# SML-230109PCB1__LCD.net
KiCad netlist of a schematic drawn in Altium Designer
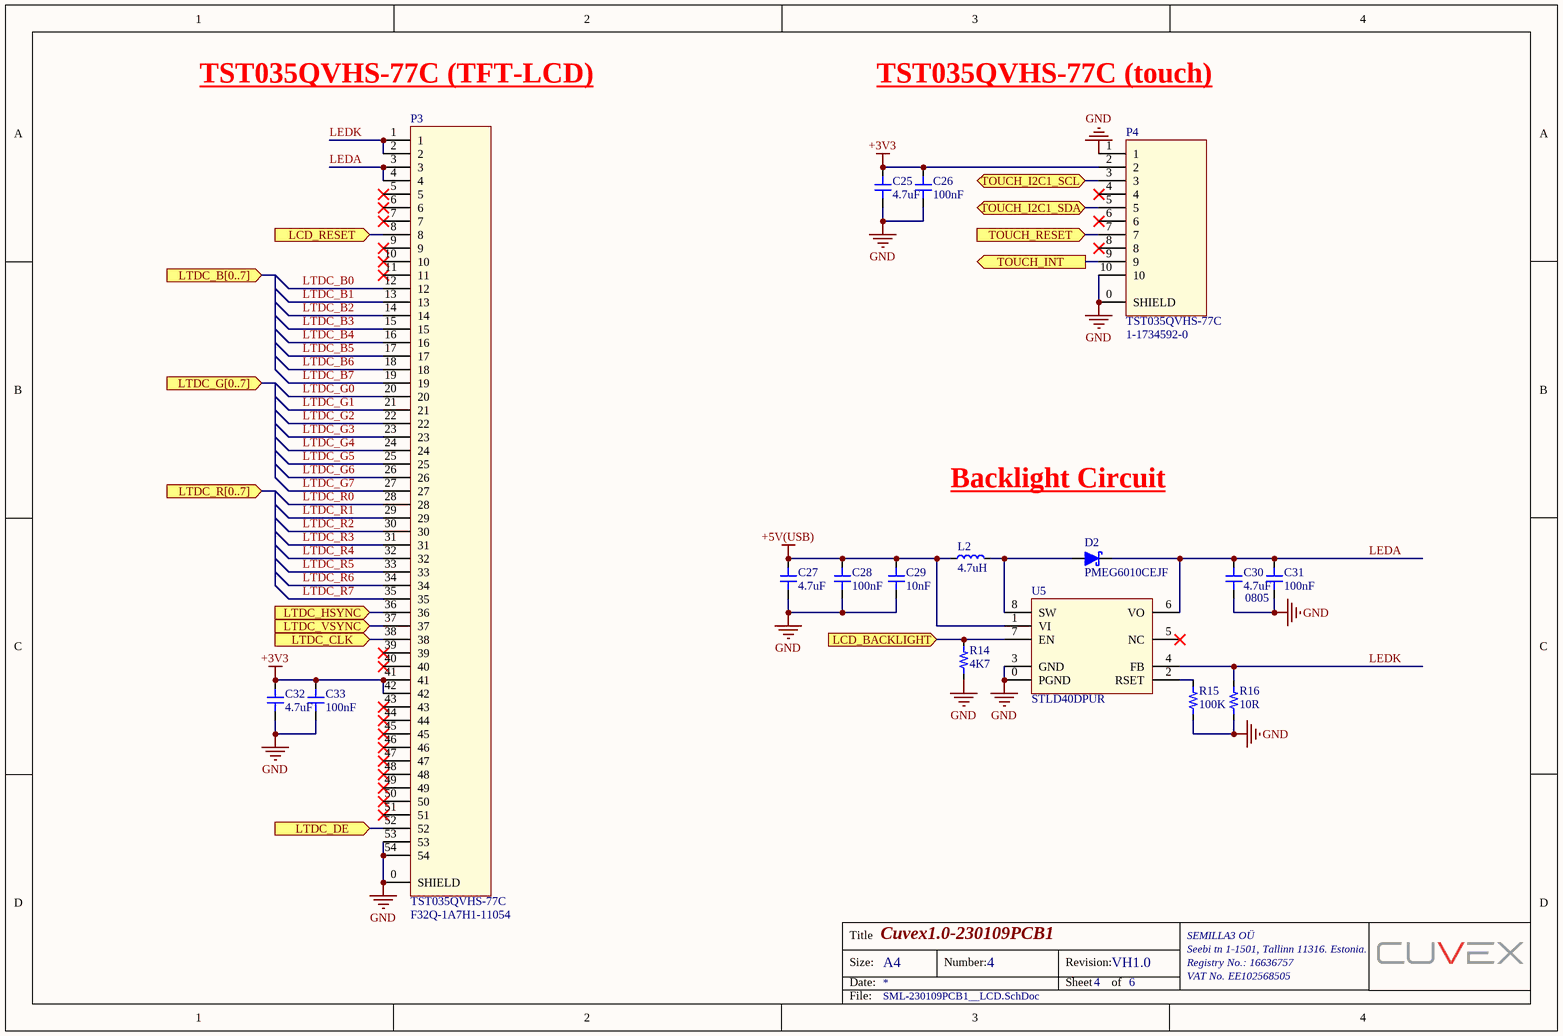
[diagram p0: SML-230109PCB1__LCD.SchDoc]

(export (version "E")
  (design (tool "Eeschema 10.0.6"))
  (components
    (comp (ref "C25")
      (value "4.7uF")
      (footprint "[G] CAP-MLCC__0603")
      (description "CAP MLCC 0603")
      (fields (field (name "VOLTAGE") "010") (field (name "Comment") "."))
      (libsource (lib "DEB_LIB_SCH_22-03") (part "CAP_MLCC_0603"))
    )
    (comp (ref "C26")
      (value "100nF")
      (footprint "[G] CAP-MLCC__0603")
      (description "CAP MLCC 0603")
      (fields (field (name "VOLTAGE") "010") (field (name "Comment") "."))
      (libsource (lib "DEB_LIB_SCH_22-03") (part "CAP_MLCC_0603"))
    )
    (comp (ref "C27")
      (value "4.7uF")
      (footprint "[G] CAP-MLCC__0603")
      (description "CAP MLCC 0603")
      (fields (field (name "VOLTAGE") "010") (field (name "Comment") "."))
      (libsource (lib "DEB_LIB_SCH_22-03") (part "CAP_MLCC_0603"))
    )
    (comp (ref "C28")
      (value "100nF")
      (footprint "[G] CAP-MLCC__0603")
      (description "CAP MLCC 0603")
      (fields (field (name "VOLTAGE") "010") (field (name "Comment") "."))
      (libsource (lib "DEB_LIB_SCH_22-03") (part "CAP_MLCC_0603"))
    )
    (comp (ref "C29")
      (value "10nF")
      (footprint "[G] CAP-MLCC__0603")
      (description "CAP MLCC 0603")
      (fields (field (name "VOLTAGE") "010") (field (name "Comment") "."))
      (libsource (lib "DEB_LIB_SCH_22-03") (part "CAP_MLCC_0603"))
    )
    (comp (ref "C30")
      (value "4.7uF")
      (footprint "[G] CAP-MLCC__0805")
      (description "CAP MLCC 0805")
      (fields
        (field (name "VOLTAGE") "050")
        (field (name "[06] - PACKAGE") "0805")
        (field (name "Comment") ".")
      )
      (libsource (lib "DEB_LIB_SCH_22-03") (part "CAP_MLCC_0805"))
    )
    (comp (ref "C31")
      (value "100nF")
      (footprint "[G] CAP-MLCC__0603")
      (description "CAP MLCC 0603")
      (fields (field (name "VOLTAGE") "050") (field (name "Comment") "."))
      (libsource (lib "DEB_LIB_SCH_22-03") (part "CAP_MLCC_0603"))
    )
    (comp (ref "C32")
      (value "4.7uF")
      (footprint "[G] CAP-MLCC__0603")
      (description "CAP MLCC 0603")
      (fields (field (name "VOLTAGE") "010") (field (name "Comment") "."))
      (libsource (lib "DEB_LIB_SCH_22-03") (part "CAP_MLCC_0603"))
    )
    (comp (ref "C33")
      (value "100nF")
      (footprint "[G] CAP-MLCC__0603")
      (description "CAP MLCC 0603")
      (fields (field (name "VOLTAGE") "010") (field (name "Comment") "."))
      (libsource (lib "DEB_LIB_SCH_22-03") (part "CAP_MLCC_0603"))
    )
    (comp (ref "D2")
      (value ".")
      (footprint "[G] SOD-323__W")
      (description "DIODE SCHOTTKY & RECTIFIER, SOD-323F, Vf=570mV, If=1A, Vr=60V, Ir=50uA")
      (fields (field (name "[01] - MPN CODE") "PMEG6010CEJF"))
      (libsource (lib "DEB_LIB_SCH_22-03") (part "PMEG6010CEJF"))
    )
    (comp (ref "L2")
      (value "4.7uH")
      (footprint "IND__LQH32PH__3'2x2'5x1'55mm")
      (description "IND Murata, LQH32PHxxx, 4'7uH")
      (fields (field (name "Comment") "."))
      (libsource (lib "DEB_LIB_SCH_22-03") (part "LQH32PH4R7NN0L"))
    )
    (comp (ref "P3")
      (value ".")
      (footprint "CONN-FFC/FPC__AMPHENOL__54P-TOP__F32Q-1A7H1-11054__INV")
      (description "CONN FFC/FPC, AMPHENOL, right angle, 54pin (0'5mm), top contact")
      (fields (field (name "TFT-LCD") "TST035QVHS-77C") (field (name "[01] - MPN CODE") "F32Q-1A7H1-11054"))
      (libsource (lib "DEB_LIB_SCH_22-03") (part "F32Q-1A7H1-11054"))
    )
    (comp (ref "P4")
      (value ".")
      (footprint "CONN-FFC/FPC__TE__10P-BOT__1-1734592-0__INV")
      (description "CONN FFC/FPC, TE, right angle, 10pin (0'5mm), bot contact")
      (fields (field (name "TFT-LCD") "TST035QVHS-77C") (field (name "[01] - MPN CODE") "1-1734592-0"))
      (libsource (lib "DEB_LIB_SCH_22-03") (part "1-1734592-0"))
    )
    (comp (ref "R14")
      (value "4K7")
      (footprint "[G] RES-CHIP__0603")
      (description "RES SMD 0603 [G]")
      (fields (field (name "TOLERANCE") "1%") (field (name "Comment") "."))
      (libsource (lib "DEB_LIB_SCH_22-03") (part "RES_SMD_0603"))
    )
    (comp (ref "R15")
      (value "100K")
      (footprint "[G] RES-CHIP__0603")
      (description "RES SMD 0603 [G]")
      (fields (field (name "TOLERANCE") "1%") (field (name "Comment") "."))
      (libsource (lib "DEB_LIB_SCH_22-03") (part "RES_SMD_0603"))
    )
    (comp (ref "R16")
      (value "10R")
      (footprint "[G] RES-CHIP__0603")
      (description "RES SMD 0603 [G]")
      (fields (field (name "TOLERANCE") "1%") (field (name "Comment") "."))
      (libsource (lib "DEB_LIB_SCH_22-03") (part "RES_SMD_0603"))
    )
    (comp (ref "U5")
      (value ".")
      (footprint "IC-DRV-LED__STLD40DPUR__QFN-8(3X3)")
      (description "IC DRV LED BOOST, 1 output, Vdd=3'00-5'5V, Vout≤37V, Iout=20mA")
      (fields (field (name "[01] - MPN CODE") "STLD40DPUR"))
      (libsource (lib "DEB_LIB_SCH_22-03") (part "STLD40DPUR"))
    )
  )
  (nets
    (net (code "1") (name "+3V3") (class "Default")
      (node (ref "C25") (pin "2") (pinfunction "2_2") (pintype "passive"))
      (node (ref "C26") (pin "2") (pinfunction "2_2") (pintype "passive"))
      (node (ref "C32") (pin "2") (pinfunction "2_2") (pintype "passive"))
      (node (ref "C33") (pin "2") (pinfunction "2_2") (pintype "passive"))
      (node (ref "P3") (pin "41") (pinfunction "41_41") (pintype "passive"))
      (node (ref "P3") (pin "42") (pinfunction "42_42") (pintype "passive"))
      (node (ref "P4") (pin "2") (pinfunction "2_2") (pintype "passive"))
    )
    (net (code "2") (name "+5V(USB)") (class "Default")
      (node (ref "C27") (pin "2") (pinfunction "2_2") (pintype "passive"))
      (node (ref "C28") (pin "2") (pinfunction "2_2") (pintype "passive"))
      (node (ref "C29") (pin "2") (pinfunction "2_2") (pintype "passive"))
      (node (ref "L2") (pin "1") (pinfunction "1_1") (pintype "passive"))
      (node (ref "U5") (pin "1") (pinfunction "VI_1") (pintype "passive"))
    )
    (net (code "3") (name "/LCD_BACKLIGHT") (class "Default")
      (node (ref "R14") (pin "1") (pinfunction "1_1") (pintype "passive"))
      (node (ref "U5") (pin "7") (pinfunction "EN_7") (pintype "passive"))
    )
    (net (code "4") (name "/LCD_RESET") (class "Default")
      (node (ref "P3") (pin "8") (pinfunction "8_8") (pintype "passive"))
    )
    (net (code "5") (name "/LEDA") (class "Default")
      (node (ref "C30") (pin "2") (pinfunction "2_2") (pintype "passive"))
      (node (ref "C31") (pin "2") (pinfunction "2_2") (pintype "passive"))
      (node (ref "D2") (pin "K") (pinfunction "K_K") (pintype "passive"))
      (node (ref "P3") (pin "3") (pinfunction "3_3") (pintype "passive"))
      (node (ref "P3") (pin "4") (pinfunction "4_4") (pintype "passive"))
      (node (ref "U5") (pin "6") (pinfunction "VO_6") (pintype "passive"))
    )
    (net (code "6") (name "/LEDK") (class "Default")
      (node (ref "P3") (pin "1") (pinfunction "1_1") (pintype "passive"))
      (node (ref "P3") (pin "2") (pinfunction "2_2") (pintype "passive"))
      (node (ref "R16") (pin "2") (pinfunction "2_2") (pintype "passive"))
      (node (ref "U5") (pin "4") (pinfunction "FB_4") (pintype "passive"))
    )
    (net (code "7") (name "/LTDC_B0") (class "Default")
      (node (ref "P3") (pin "12") (pinfunction "12_12") (pintype "passive"))
    )
    (net (code "8") (name "/LTDC_B1") (class "Default")
      (node (ref "P3") (pin "13") (pinfunction "13_13") (pintype "passive"))
    )
    (net (code "9") (name "/LTDC_B2") (class "Default")
      (node (ref "P3") (pin "14") (pinfunction "14_14") (pintype "passive"))
    )
    (net (code "10") (name "/LTDC_B3") (class "Default")
      (node (ref "P3") (pin "15") (pinfunction "15_15") (pintype "passive"))
    )
    (net (code "11") (name "/LTDC_B4") (class "Default")
      (node (ref "P3") (pin "16") (pinfunction "16_16") (pintype "passive"))
    )
    (net (code "12") (name "/LTDC_B5") (class "Default")
      (node (ref "P3") (pin "17") (pinfunction "17_17") (pintype "passive"))
    )
    (net (code "13") (name "/LTDC_B6") (class "Default")
      (node (ref "P3") (pin "18") (pinfunction "18_18") (pintype "passive"))
    )
    (net (code "14") (name "/LTDC_B7") (class "Default")
      (node (ref "P3") (pin "19") (pinfunction "19_19") (pintype "passive"))
    )
    (net (code "16") (name "/LTDC_CLK") (class "Default")
      (node (ref "P3") (pin "38") (pinfunction "38_38") (pintype "passive"))
    )
    (net (code "17") (name "/LTDC_DE") (class "Default")
      (node (ref "P3") (pin "52") (pinfunction "52_52") (pintype "passive"))
    )
    (net (code "18") (name "/LTDC_G0") (class "Default")
      (node (ref "P3") (pin "20") (pinfunction "20_20") (pintype "passive"))
    )
    (net (code "19") (name "/LTDC_G1") (class "Default")
      (node (ref "P3") (pin "21") (pinfunction "21_21") (pintype "passive"))
    )
    (net (code "20") (name "/LTDC_G2") (class "Default")
      (node (ref "P3") (pin "22") (pinfunction "22_22") (pintype "passive"))
    )
    (net (code "21") (name "/LTDC_G3") (class "Default")
      (node (ref "P3") (pin "23") (pinfunction "23_23") (pintype "passive"))
    )
    (net (code "22") (name "/LTDC_G4") (class "Default")
      (node (ref "P3") (pin "24") (pinfunction "24_24") (pintype "passive"))
    )
    (net (code "23") (name "/LTDC_G5") (class "Default")
      (node (ref "P3") (pin "25") (pinfunction "25_25") (pintype "passive"))
    )
    (net (code "24") (name "/LTDC_G6") (class "Default")
      (node (ref "P3") (pin "26") (pinfunction "26_26") (pintype "passive"))
    )
    (net (code "25") (name "/LTDC_G7") (class "Default")
      (node (ref "P3") (pin "27") (pinfunction "27_27") (pintype "passive"))
    )
    (net (code "27") (name "/LTDC_HSYNC") (class "Default")
      (node (ref "P3") (pin "36") (pinfunction "36_36") (pintype "passive"))
    )
    (net (code "28") (name "/LTDC_R0") (class "Default")
      (node (ref "P3") (pin "28") (pinfunction "28_28") (pintype "passive"))
    )
    (net (code "29") (name "/LTDC_R1") (class "Default")
      (node (ref "P3") (pin "29") (pinfunction "29_29") (pintype "passive"))
    )
    (net (code "30") (name "/LTDC_R2") (class "Default")
      (node (ref "P3") (pin "30") (pinfunction "30_30") (pintype "passive"))
    )
    (net (code "31") (name "/LTDC_R3") (class "Default")
      (node (ref "P3") (pin "31") (pinfunction "31_31") (pintype "passive"))
    )
    (net (code "32") (name "/LTDC_R4") (class "Default")
      (node (ref "P3") (pin "32") (pinfunction "32_32") (pintype "passive"))
    )
    (net (code "33") (name "/LTDC_R5") (class "Default")
      (node (ref "P3") (pin "33") (pinfunction "33_33") (pintype "passive"))
    )
    (net (code "34") (name "/LTDC_R6") (class "Default")
      (node (ref "P3") (pin "34") (pinfunction "34_34") (pintype "passive"))
    )
    (net (code "35") (name "/LTDC_R7") (class "Default")
      (node (ref "P3") (pin "35") (pinfunction "35_35") (pintype "passive"))
    )
    (net (code "37") (name "/LTDC_VSYNC") (class "Default")
      (node (ref "P3") (pin "37") (pinfunction "37_37") (pintype "passive"))
    )
    (net (code "38") (name "/TOUCH_I2C1_SCL") (class "Default")
      (node (ref "P4") (pin "3") (pinfunction "3_3") (pintype "passive"))
    )
    (net (code "39") (name "/TOUCH_I2C1_SDA") (class "Default")
      (node (ref "P4") (pin "5") (pinfunction "5_5") (pintype "passive"))
    )
    (net (code "40") (name "/TOUCH_INT") (class "Default")
      (node (ref "P4") (pin "9") (pinfunction "9_9") (pintype "passive"))
    )
    (net (code "41") (name "/TOUCH_RESET") (class "Default")
      (node (ref "P4") (pin "7") (pinfunction "7_7") (pintype "passive"))
    )
    (net (code "42") (name "GND") (class "Default")
      (node (ref "C25") (pin "1") (pinfunction "1_1") (pintype "passive"))
      (node (ref "C26") (pin "1") (pinfunction "1_1") (pintype "passive"))
      (node (ref "C27") (pin "1") (pinfunction "1_1") (pintype "passive"))
      (node (ref "C28") (pin "1") (pinfunction "1_1") (pintype "passive"))
      (node (ref "C29") (pin "1") (pinfunction "1_1") (pintype "passive"))
      (node (ref "C30") (pin "1") (pinfunction "1_1") (pintype "passive"))
      (node (ref "C31") (pin "1") (pinfunction "1_1") (pintype "passive"))
      (node (ref "C32") (pin "1") (pinfunction "1_1") (pintype "passive"))
      (node (ref "C33") (pin "1") (pinfunction "1_1") (pintype "passive"))
      (node (ref "P3") (pin "0") (pinfunction "SHIELD_0") (pintype "passive"))
      (node (ref "P3") (pin "53") (pinfunction "53_53") (pintype "passive"))
      (node (ref "P3") (pin "54") (pinfunction "54_54") (pintype "passive"))
      (node (ref "P4") (pin "0") (pinfunction "SHIELD_0") (pintype "passive"))
      (node (ref "P4") (pin "1") (pinfunction "1_1") (pintype "passive"))
      (node (ref "P4") (pin "10") (pinfunction "10_10") (pintype "passive"))
      (node (ref "R14") (pin "2") (pinfunction "2_2") (pintype "passive"))
      (node (ref "R15") (pin "1") (pinfunction "1_1") (pintype "passive"))
      (node (ref "R16") (pin "1") (pinfunction "1_1") (pintype "passive"))
      (node (ref "U5") (pin "0") (pinfunction "PGND_0") (pintype "passive"))
      (node (ref "U5") (pin "3") (pinfunction "GND_3") (pintype "passive"))
    )
    (net (code "43") (name "Net-(U5-RSET)") (class "Default")
      (node (ref "R15") (pin "2") (pinfunction "2_2") (pintype "passive"))
      (node (ref "U5") (pin "2") (pinfunction "RSET_2") (pintype "passive"))
    )
    (net (code "44") (name "Net-(U5-SW)") (class "Default")
      (node (ref "D2") (pin "A") (pinfunction "A_A") (pintype "passive"))
      (node (ref "L2") (pin "2") (pinfunction "2_2") (pintype "passive"))
      (node (ref "U5") (pin "8") (pinfunction "SW_8") (pintype "passive"))
    )
    (net (code "45") (name "unconnected-(P3-Pad5)") (class "Default")
      (node (ref "P3") (pin "5") (pinfunction "5_5") (pintype "passive+no_connect"))
    )
    (net (code "46") (name "unconnected-(P3-Pad6)") (class "Default")
      (node (ref "P3") (pin "6") (pinfunction "6_6") (pintype "passive+no_connect"))
    )
    (net (code "47") (name "unconnected-(P3-Pad7)") (class "Default")
      (node (ref "P3") (pin "7") (pinfunction "7_7") (pintype "passive+no_connect"))
    )
    (net (code "48") (name "unconnected-(P3-Pad9)") (class "Default")
      (node (ref "P3") (pin "9") (pinfunction "9_9") (pintype "passive+no_connect"))
    )
    (net (code "49") (name "unconnected-(P3-Pad10)") (class "Default")
      (node (ref "P3") (pin "10") (pinfunction "10_10") (pintype "passive+no_connect"))
    )
    (net (code "50") (name "unconnected-(P3-Pad11)") (class "Default")
      (node (ref "P3") (pin "11") (pinfunction "11_11") (pintype "passive+no_connect"))
    )
    (net (code "51") (name "unconnected-(P3-Pad39)") (class "Default")
      (node (ref "P3") (pin "39") (pinfunction "39_39") (pintype "passive+no_connect"))
    )
    (net (code "52") (name "unconnected-(P3-Pad40)") (class "Default")
      (node (ref "P3") (pin "40") (pinfunction "40_40") (pintype "passive+no_connect"))
    )
    (net (code "53") (name "unconnected-(P3-Pad43)") (class "Default")
      (node (ref "P3") (pin "43") (pinfunction "43_43") (pintype "passive+no_connect"))
    )
    (net (code "54") (name "unconnected-(P3-Pad44)") (class "Default")
      (node (ref "P3") (pin "44") (pinfunction "44_44") (pintype "passive+no_connect"))
    )
    (net (code "55") (name "unconnected-(P3-Pad45)") (class "Default")
      (node (ref "P3") (pin "45") (pinfunction "45_45") (pintype "passive+no_connect"))
    )
    (net (code "56") (name "unconnected-(P3-Pad46)") (class "Default")
      (node (ref "P3") (pin "46") (pinfunction "46_46") (pintype "passive+no_connect"))
    )
    (net (code "57") (name "unconnected-(P3-Pad47)") (class "Default")
      (node (ref "P3") (pin "47") (pinfunction "47_47") (pintype "passive+no_connect"))
    )
    (net (code "58") (name "unconnected-(P3-Pad48)") (class "Default")
      (node (ref "P3") (pin "48") (pinfunction "48_48") (pintype "passive+no_connect"))
    )
    (net (code "59") (name "unconnected-(P3-Pad49)") (class "Default")
      (node (ref "P3") (pin "49") (pinfunction "49_49") (pintype "passive+no_connect"))
    )
    (net (code "60") (name "unconnected-(P3-Pad50)") (class "Default")
      (node (ref "P3") (pin "50") (pinfunction "50_50") (pintype "passive+no_connect"))
    )
    (net (code "61") (name "unconnected-(P3-Pad51)") (class "Default")
      (node (ref "P3") (pin "51") (pinfunction "51_51") (pintype "passive+no_connect"))
    )
    (net (code "62") (name "unconnected-(P4-Pad4)") (class "Default")
      (node (ref "P4") (pin "4") (pinfunction "4_4") (pintype "passive+no_connect"))
    )
    (net (code "63") (name "unconnected-(P4-Pad6)") (class "Default")
      (node (ref "P4") (pin "6") (pinfunction "6_6") (pintype "passive+no_connect"))
    )
    (net (code "64") (name "unconnected-(P4-Pad8)") (class "Default")
      (node (ref "P4") (pin "8") (pinfunction "8_8") (pintype "passive+no_connect"))
    )
    (net (code "65") (name "unconnected-(U5-NC-Pad5)") (class "Default")
      (node (ref "U5") (pin "5") (pinfunction "NC_5") (pintype "passive+no_connect"))
    )
  )
)
